# MineralFire.net
KiCad netlist of a schematic drawn in EAGLE
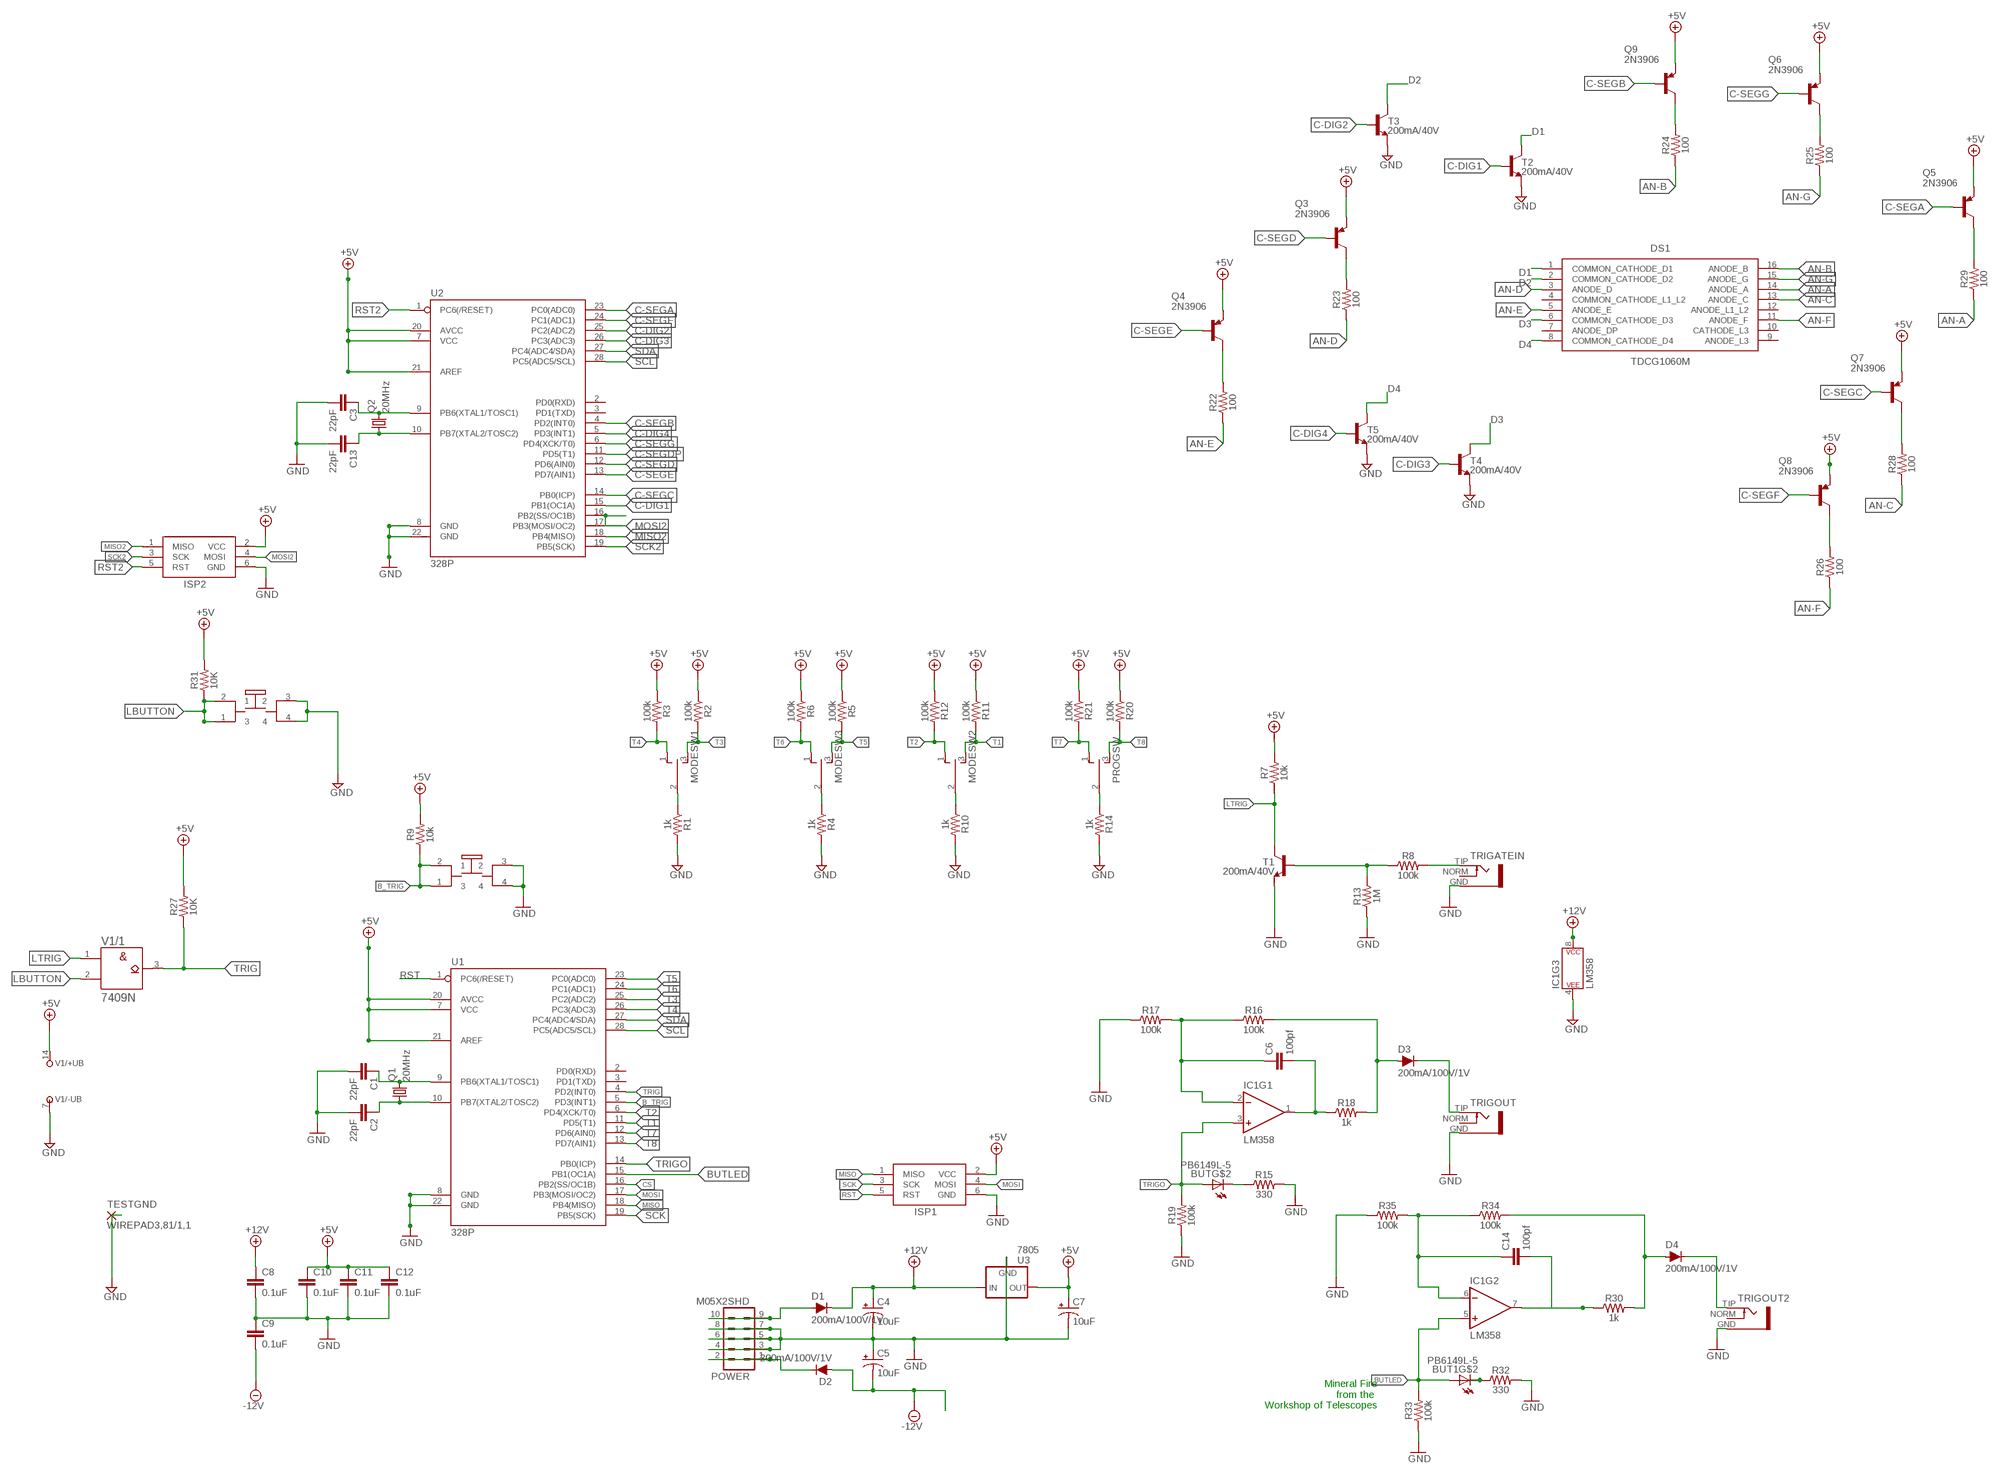
[diagram p0: schematic, sheet 1]

(export (version "E")
  (design (tool "Eeschema 10.0.6"))
  (components
    (comp (ref "BUT")
      (value "PB6149L-5")
      (footprint "eagle-import:PB6149L")
      (libsource (lib "eagle-import") (part "PB6149L-5"))
    )
    (comp (ref "BUT1")
      (value "PB6149L-5")
      (footprint "eagle-import:PB6149L")
      (libsource (lib "eagle-import") (part "PB6149L-5"))
    )
    (comp (ref "C1")
      (value "22pF")
      (footprint "eagle-import:CAP-PTH-2.54")
      (libsource (lib "eagle-import") (part "22PF-PTH-2.54MM-200V-5%"))
    )
    (comp (ref "C2")
      (value "22pF")
      (footprint "eagle-import:CAP-PTH-2.54")
      (libsource (lib "eagle-import") (part "22PF-PTH-2.54MM-200V-5%"))
    )
    (comp (ref "C3")
      (value "22pF")
      (footprint "eagle-import:CAP-PTH-2.54")
      (libsource (lib "eagle-import") (part "22PF-PTH-2.54MM-200V-5%"))
    )
    (comp (ref "C4")
      (value "10uF")
      (footprint "eagle-import:CPOL-RADIAL-2.5MM-5MM")
      (libsource (lib "eagle-import") (part "10UF-POLAR-RADIAL-2.5MM-25V-20%"))
    )
    (comp (ref "C5")
      (value "10uF")
      (footprint "eagle-import:CPOL-RADIAL-2.5MM-5MM")
      (libsource (lib "eagle-import") (part "10UF-POLAR-RADIAL-2.5MM-25V-20%"))
    )
    (comp (ref "C6")
      (value "100pf")
      (footprint "eagle-import:C075-032X103")
      (libsource (lib "eagle-import") (part "C-EU075-032X103"))
    )
    (comp (ref "C7")
      (value "10uF")
      (footprint "eagle-import:CPOL-RADIAL-2.5MM-5MM")
      (libsource (lib "eagle-import") (part "10UF-POLAR-RADIAL-2.5MM-25V-20%"))
    )
    (comp (ref "C8")
      (value "0.1uF")
      (footprint "eagle-import:CAP-PTH-SMALL-KIT")
      (libsource (lib "eagle-import") (part "0.1UF-KIT-EZ-50V-20%"))
    )
    (comp (ref "C9")
      (value "0.1uF")
      (footprint "eagle-import:CAP-PTH-SMALL-KIT")
      (libsource (lib "eagle-import") (part "0.1UF-KIT-EZ-50V-20%"))
    )
    (comp (ref "C10")
      (value "0.1uF")
      (footprint "eagle-import:CAP-PTH-SMALL-KIT")
      (libsource (lib "eagle-import") (part "0.1UF-KIT-EZ-50V-20%"))
    )
    (comp (ref "C11")
      (value "0.1uF")
      (footprint "eagle-import:CAP-PTH-SMALL-KIT")
      (libsource (lib "eagle-import") (part "0.1UF-KIT-EZ-50V-20%"))
    )
    (comp (ref "C12")
      (value "0.1uF")
      (footprint "eagle-import:CAP-PTH-SMALL-KIT")
      (libsource (lib "eagle-import") (part "0.1UF-KIT-EZ-50V-20%"))
    )
    (comp (ref "C13")
      (value "22pF")
      (footprint "eagle-import:CAP-PTH-2.54")
      (libsource (lib "eagle-import") (part "22PF-PTH-2.54MM-200V-5%"))
    )
    (comp (ref "C14")
      (value "100pf")
      (footprint "eagle-import:C075-032X103")
      (libsource (lib "eagle-import") (part "C-EU075-032X103"))
    )
    (comp (ref "D1")
      (value "200mA/100V/1V")
      (footprint "eagle-import:DIODE-1N4148")
      (libsource (lib "eagle-import") (part "DIODE-1N4148"))
    )
    (comp (ref "D2")
      (value "200mA/100V/1V")
      (footprint "eagle-import:DIODE-1N4148")
      (libsource (lib "eagle-import") (part "DIODE-1N4148"))
    )
    (comp (ref "D3")
      (value "200mA/100V/1V")
      (footprint "eagle-import:DIODE-1N4148")
      (libsource (lib "eagle-import") (part "DIODE-1N4148"))
    )
    (comp (ref "D4")
      (value "200mA/100V/1V")
      (footprint "eagle-import:DIODE-1N4148")
      (libsource (lib "eagle-import") (part "DIODE-1N4148"))
    )
    (comp (ref "DS1")
      (value "TDCG1060M")
      (footprint "eagle-import:DIPS1016W50P254L4020H700Q16N")
      (fields (field (name "RS_PART_NUMBER") "8187530P"))
      (libsource (lib "eagle-import") (part "TDCG1060M"))
    )
    (comp (ref "IC1")
      (value "LM358")
      (footprint "eagle-import:DIP08")
      (libsource (lib "eagle-import") (part "LM358"))
    )
    (comp (ref "ISP1")
      (value "AVRISP-6")
      (footprint "eagle-import:AVRISP")
      (libsource (lib "eagle-import") (part "AVRISP-6"))
    )
    (comp (ref "ISP2")
      (value "AVRISP-6")
      (footprint "eagle-import:AVRISP")
      (libsource (lib "eagle-import") (part "AVRISP-6"))
    )
    (comp (ref "MODESW1")
      (value "TOGGLE_ON_OFF_ON")
      (footprint "eagle-import:TOGGLE_ON_OFF_ON")
      (libsource (lib "eagle-import") (part "TOGGLE_ON_OFF_ON"))
    )
    (comp (ref "MODESW2")
      (value "TOGGLE_ON_OFF_ON")
      (footprint "eagle-import:TOGGLE_ON_OFF_ON")
      (libsource (lib "eagle-import") (part "TOGGLE_ON_OFF_ON"))
    )
    (comp (ref "MODESW3")
      (value "TOGGLE_ON_OFF_ON")
      (footprint "eagle-import:TOGGLE_ON_OFF_ON")
      (libsource (lib "eagle-import") (part "TOGGLE_ON_OFF_ON"))
    )
    (comp (ref "POWER")
      (value "M05X2SHD")
      (footprint "eagle-import:2X5-SHROUDED")
      (libsource (lib "eagle-import") (part "M05X2SHD"))
    )
    (comp (ref "PROGSW")
      (value "TOGGLE_ON_OFF_ON")
      (footprint "eagle-import:TOGGLE_ON_OFF_ON")
      (libsource (lib "eagle-import") (part "TOGGLE_ON_OFF_ON"))
    )
    (comp (ref "Q1")
      (value "20MHz")
      (footprint "eagle-import:HC49U70")
      (libsource (lib "eagle-import") (part "CRYSTALHC49U70"))
    )
    (comp (ref "Q2")
      (value "20MHz")
      (footprint "eagle-import:HC49U70")
      (libsource (lib "eagle-import") (part "CRYSTALHC49U70"))
    )
    (comp (ref "Q3")
      (value "2N3906")
      (footprint "eagle-import:TO92")
      (libsource (lib "eagle-import") (part "2N3906"))
    )
    (comp (ref "Q4")
      (value "2N3906")
      (footprint "eagle-import:TO92")
      (libsource (lib "eagle-import") (part "2N3906"))
    )
    (comp (ref "Q5")
      (value "2N3906")
      (footprint "eagle-import:TO92")
      (libsource (lib "eagle-import") (part "2N3906"))
    )
    (comp (ref "Q6")
      (value "2N3906")
      (footprint "eagle-import:TO92")
      (libsource (lib "eagle-import") (part "2N3906"))
    )
    (comp (ref "Q7")
      (value "2N3906")
      (footprint "eagle-import:TO92")
      (libsource (lib "eagle-import") (part "2N3906"))
    )
    (comp (ref "Q8")
      (value "2N3906")
      (footprint "eagle-import:TO92")
      (libsource (lib "eagle-import") (part "2N3906"))
    )
    (comp (ref "Q9")
      (value "2N3906")
      (footprint "eagle-import:TO92")
      (libsource (lib "eagle-import") (part "2N3906"))
    )
    (comp (ref "R1")
      (value "1k")
      (footprint "eagle-import:AXIAL-0.3")
      (libsource (lib "eagle-import") (part "1KOHM-HORIZ-1/4W-5%"))
    )
    (comp (ref "R2")
      (value "100k")
      (footprint "eagle-import:AXIAL-0.3")
      (libsource (lib "eagle-import") (part "100KOHM-HORIZ-1/4W-5%"))
    )
    (comp (ref "R3")
      (value "100k")
      (footprint "eagle-import:AXIAL-0.3")
      (libsource (lib "eagle-import") (part "100KOHM-HORIZ-1/4W-5%"))
    )
    (comp (ref "R4")
      (value "1k")
      (footprint "eagle-import:AXIAL-0.3")
      (libsource (lib "eagle-import") (part "1KOHM-HORIZ-1/4W-5%"))
    )
    (comp (ref "R5")
      (value "100k")
      (footprint "eagle-import:AXIAL-0.3")
      (libsource (lib "eagle-import") (part "100KOHM-HORIZ-1/4W-5%"))
    )
    (comp (ref "R6")
      (value "100k")
      (footprint "eagle-import:AXIAL-0.3")
      (libsource (lib "eagle-import") (part "100KOHM-HORIZ-1/4W-5%"))
    )
    (comp (ref "R7")
      (value "10k")
      (footprint "eagle-import:AXIAL-0.3")
      (libsource (lib "eagle-import") (part "10KOHM-HORIZ-1/4W-5%"))
    )
    (comp (ref "R8")
      (value "100k")
      (footprint "eagle-import:AXIAL-0.3")
      (libsource (lib "eagle-import") (part "100KOHM-HORIZ-1/4W-5%"))
    )
    (comp (ref "R9")
      (value "10k")
      (footprint "eagle-import:AXIAL-0.3")
      (libsource (lib "eagle-import") (part "10KOHM-HORIZ-1/4W-1%"))
    )
    (comp (ref "R10")
      (value "1k")
      (footprint "eagle-import:AXIAL-0.3")
      (libsource (lib "eagle-import") (part "1KOHM-HORIZ-1/4W-5%"))
    )
    (comp (ref "R11")
      (value "100k")
      (footprint "eagle-import:AXIAL-0.3")
      (libsource (lib "eagle-import") (part "100KOHM-HORIZ-1/4W-5%"))
    )
    (comp (ref "R12")
      (value "100k")
      (footprint "eagle-import:AXIAL-0.3")
      (libsource (lib "eagle-import") (part "100KOHM-HORIZ-1/4W-5%"))
    )
    (comp (ref "R13")
      (value "1M")
      (footprint "eagle-import:AXIAL-0.3")
      (libsource (lib "eagle-import") (part "1MOHM-HORIZ-1/4W-5%"))
    )
    (comp (ref "R14")
      (value "1k")
      (footprint "eagle-import:AXIAL-0.3")
      (libsource (lib "eagle-import") (part "1KOHM-HORIZ-1/4W-5%"))
    )
    (comp (ref "R15")
      (value "330")
      (footprint "eagle-import:AXIAL-0.3")
      (libsource (lib "eagle-import") (part "330OHM-HORIZ-1/10W-5%"))
    )
    (comp (ref "R16")
      (value "100k")
      (footprint "eagle-import:AXIAL-0.3")
      (libsource (lib "eagle-import") (part "100KOHM-HORIZ-1/4W-5%"))
    )
    (comp (ref "R17")
      (value "100k")
      (footprint "eagle-import:AXIAL-0.3")
      (libsource (lib "eagle-import") (part "100KOHM-HORIZ-1/4W-5%"))
    )
    (comp (ref "R18")
      (value "1k")
      (footprint "eagle-import:AXIAL-0.3")
      (libsource (lib "eagle-import") (part "1KOHM-HORIZ-1/4W-5%"))
    )
    (comp (ref "R19")
      (value "100k")
      (footprint "eagle-import:AXIAL-0.3")
      (libsource (lib "eagle-import") (part "100KOHM-HORIZ-1/4W-5%"))
    )
    (comp (ref "R20")
      (value "100k")
      (footprint "eagle-import:AXIAL-0.3")
      (libsource (lib "eagle-import") (part "100KOHM-HORIZ-1/4W-5%"))
    )
    (comp (ref "R21")
      (value "100k")
      (footprint "eagle-import:AXIAL-0.3")
      (libsource (lib "eagle-import") (part "100KOHM-HORIZ-1/4W-5%"))
    )
    (comp (ref "R22")
      (value "100")
      (footprint "eagle-import:AXIAL-0.3EZ")
      (libsource (lib "eagle-import") (part "100OHM-HORIZ_KIT-1/4W-1%"))
    )
    (comp (ref "R23")
      (value "100")
      (footprint "eagle-import:AXIAL-0.3EZ")
      (libsource (lib "eagle-import") (part "100OHM-HORIZ_KIT-1/4W-1%"))
    )
    (comp (ref "R24")
      (value "100")
      (footprint "eagle-import:AXIAL-0.3EZ")
      (libsource (lib "eagle-import") (part "100OHM-HORIZ_KIT-1/4W-1%"))
    )
    (comp (ref "R25")
      (value "100")
      (footprint "eagle-import:AXIAL-0.3EZ")
      (libsource (lib "eagle-import") (part "100OHM-HORIZ_KIT-1/4W-1%"))
    )
    (comp (ref "R26")
      (value "100")
      (footprint "eagle-import:AXIAL-0.3EZ")
      (libsource (lib "eagle-import") (part "100OHM-HORIZ_KIT-1/4W-1%"))
    )
    (comp (ref "R27")
      (value "10K")
      (footprint "eagle-import:AXIAL-0.3EZ")
      (libsource (lib "eagle-import") (part "100OHM-HORIZ_KIT-1/4W-1%"))
    )
    (comp (ref "R28")
      (value "100")
      (footprint "eagle-import:AXIAL-0.3EZ")
      (libsource (lib "eagle-import") (part "100OHM-HORIZ_KIT-1/4W-1%"))
    )
    (comp (ref "R29")
      (value "100")
      (footprint "eagle-import:AXIAL-0.3EZ")
      (libsource (lib "eagle-import") (part "100OHM-HORIZ_KIT-1/4W-1%"))
    )
    (comp (ref "R30")
      (value "1k")
      (footprint "eagle-import:AXIAL-0.3")
      (libsource (lib "eagle-import") (part "1KOHM-HORIZ-1/4W-5%"))
    )
    (comp (ref "R31")
      (value "10K")
      (footprint "eagle-import:AXIAL-0.3EZ")
      (libsource (lib "eagle-import") (part "100OHM-HORIZ_KIT-1/4W-1%"))
    )
    (comp (ref "R32")
      (value "330")
      (footprint "eagle-import:AXIAL-0.3")
      (libsource (lib "eagle-import") (part "330OHM-HORIZ-1/10W-5%"))
    )
    (comp (ref "R33")
      (value "100k")
      (footprint "eagle-import:AXIAL-0.3")
      (libsource (lib "eagle-import") (part "100KOHM-HORIZ-1/4W-5%"))
    )
    (comp (ref "R34")
      (value "100k")
      (footprint "eagle-import:AXIAL-0.3")
      (libsource (lib "eagle-import") (part "100KOHM-HORIZ-1/4W-5%"))
    )
    (comp (ref "R35")
      (value "100k")
      (footprint "eagle-import:AXIAL-0.3")
      (libsource (lib "eagle-import") (part "100KOHM-HORIZ-1/4W-5%"))
    )
    (comp (ref "T1")
      (value "200mA/40V")
      (footprint "eagle-import:TO-92")
      (libsource (lib "eagle-import") (part "TRANS_NPN-2N3904"))
    )
    (comp (ref "T2")
      (value "200mA/40V")
      (footprint "eagle-import:TO-92")
      (libsource (lib "eagle-import") (part "TRANS_NPN-2N3904"))
    )
    (comp (ref "T3")
      (value "200mA/40V")
      (footprint "eagle-import:TO-92")
      (libsource (lib "eagle-import") (part "TRANS_NPN-2N3904"))
    )
    (comp (ref "T4")
      (value "200mA/40V")
      (footprint "eagle-import:TO-92")
      (libsource (lib "eagle-import") (part "TRANS_NPN-2N3904"))
    )
    (comp (ref "T5")
      (value "200mA/40V")
      (footprint "eagle-import:TO-92")
      (libsource (lib "eagle-import") (part "TRANS_NPN-2N3904"))
    )
    (comp (ref "TESTGND")
      (value "WIREPAD3,81/1,1")
      (footprint "eagle-import:3,81_1,1")
      (libsource (lib "eagle-import") (part "WIREPAD3,81/1,1"))
    )
    (comp (ref "TRIGATEIN")
      (value "S_JACK")
      (footprint "eagle-import:S_JACK")
      (libsource (lib "eagle-import") (part "S_JACK"))
    )
    (comp (ref "TRIGOUT")
      (value "S_JACK")
      (footprint "eagle-import:S_JACK")
      (libsource (lib "eagle-import") (part "S_JACK"))
    )
    (comp (ref "TRIGOUT2")
      (value "S_JACK")
      (footprint "eagle-import:S_JACK")
      (libsource (lib "eagle-import") (part "S_JACK"))
    )
    (comp (ref "U1")
      (value "328P")
      (footprint "eagle-import:DIP28")
      (libsource (lib "eagle-import") (part "ATMEGA328P_PDIP"))
    )
    (comp (ref "U2")
      (value "328P")
      (footprint "eagle-import:DIP28")
      (libsource (lib "eagle-import") (part "ATMEGA328P_PDIP"))
    )
    (comp (ref "U3")
      (value "7805")
      (footprint "eagle-import:TO-220-ALT")
      (libsource (lib "eagle-import") (part "V_REG_78XX-TO-220"))
    )
    (comp (ref "V1")
      (value "7409N")
      (footprint "eagle-import:DIL14")
      (libsource (lib "eagle-import") (part "7409N"))
    )
  )
  (nets
    (net (code "1") (name "+5V") (class "Default")
      (node (ref "C10") (pin "1") (pinfunction "1_1") (pintype "passive"))
      (node (ref "C11") (pin "1") (pinfunction "1_1") (pintype "passive"))
      (node (ref "C12") (pin "1") (pinfunction "1_1") (pintype "passive"))
      (node (ref "C7") (pin "1") (pinfunction "+_1") (pintype "passive"))
      (node (ref "ISP1") (pin "2") (pinfunction "VCC_2") (pintype "power_in"))
      (node (ref "ISP2") (pin "2") (pinfunction "VCC_2") (pintype "power_in"))
      (node (ref "Q3") (pin "3") (pinfunction "E_3") (pintype "passive"))
      (node (ref "Q4") (pin "3") (pinfunction "E_3") (pintype "passive"))
      (node (ref "Q5") (pin "3") (pinfunction "E_3") (pintype "passive"))
      (node (ref "Q6") (pin "3") (pinfunction "E_3") (pintype "passive"))
      (node (ref "Q7") (pin "3") (pinfunction "E_3") (pintype "passive"))
      (node (ref "Q8") (pin "3") (pinfunction "E_3") (pintype "passive"))
      (node (ref "Q9") (pin "3") (pinfunction "E_3") (pintype "passive"))
      (node (ref "R11") (pin "P$1") (pinfunction "1_P$1") (pintype "passive"))
      (node (ref "R12") (pin "P$1") (pinfunction "1_P$1") (pintype "passive"))
      (node (ref "R2") (pin "P$1") (pinfunction "1_P$1") (pintype "passive"))
      (node (ref "R20") (pin "P$1") (pinfunction "1_P$1") (pintype "passive"))
      (node (ref "R21") (pin "P$1") (pinfunction "1_P$1") (pintype "passive"))
      (node (ref "R27") (pin "P$2") (pinfunction "2_P$2") (pintype "passive"))
      (node (ref "R3") (pin "P$1") (pinfunction "1_P$1") (pintype "passive"))
      (node (ref "R31") (pin "P$2") (pinfunction "2_P$2") (pintype "passive"))
      (node (ref "R5") (pin "P$1") (pinfunction "1_P$1") (pintype "passive"))
      (node (ref "R6") (pin "P$1") (pinfunction "1_P$1") (pintype "passive"))
      (node (ref "R7") (pin "P$2") (pinfunction "2_P$2") (pintype "passive"))
      (node (ref "R9") (pin "P$2") (pinfunction "2_P$2") (pintype "passive"))
      (node (ref "U1") (pin "20") (pinfunction "AVCC_20") (pintype "bidirectional"))
      (node (ref "U1") (pin "21") (pinfunction "AREF_21") (pintype "bidirectional"))
      (node (ref "U1") (pin "7") (pinfunction "VCC_7") (pintype "bidirectional"))
      (node (ref "U2") (pin "20") (pinfunction "AVCC_20") (pintype "bidirectional"))
      (node (ref "U2") (pin "21") (pinfunction "AREF_21") (pintype "bidirectional"))
      (node (ref "U2") (pin "7") (pinfunction "VCC_7") (pintype "bidirectional"))
      (node (ref "U3") (pin "OUT") (pinfunction "OUT_OUT") (pintype "passive"))
      (node (ref "V1") (pin "14") (pinfunction "+UB_14") (pintype "power_in"))
    )
    (net (code "2") (name "+12V") (class "Default")
      (node (ref "C4") (pin "1") (pinfunction "+_1") (pintype "passive"))
      (node (ref "C8") (pin "1") (pinfunction "1_1") (pintype "passive"))
      (node (ref "D1") (pin "C") (pinfunction "C_C") (pintype "passive"))
      (node (ref "IC1") (pin "8") (pinfunction "P$V+_8") (pintype "bidirectional"))
      (node (ref "U3") (pin "IN") (pinfunction "IN_IN") (pintype "input"))
    )
    (net (code "3") (name "-12V") (class "Default")
      (node (ref "C5") (pin "2") (pinfunction "-_2") (pintype "passive"))
      (node (ref "C9") (pin "2") (pinfunction "2_2") (pintype "passive"))
      (node (ref "D2") (pin "A") (pinfunction "A_A") (pintype "passive"))
    )
    (net (code "4") (name "/D1") (class "Default")
      (node (ref "DS1") (pin "1") (pinfunction "COMMON_CATHODE_D1_1") (pintype "input"))
      (node (ref "T2") (pin "3") (pinfunction "C_3") (pintype "passive"))
    )
    (net (code "5") (name "/D2") (class "Default")
      (node (ref "DS1") (pin "2") (pinfunction "COMMON_CATHODE_D2_2") (pintype "input"))
      (node (ref "T3") (pin "3") (pinfunction "C_3") (pintype "passive"))
    )
    (net (code "6") (name "/D3") (class "Default")
      (node (ref "DS1") (pin "6") (pinfunction "COMMON_CATHODE_D3_6") (pintype "input"))
      (node (ref "T4") (pin "3") (pinfunction "C_3") (pintype "passive"))
    )
    (net (code "7") (name "/D4") (class "Default")
      (node (ref "DS1") (pin "8") (pinfunction "COMMON_CATHODE_D4_8") (pintype "input"))
      (node (ref "T5") (pin "3") (pinfunction "C_3") (pintype "passive"))
    )
    (net (code "8") (name "AN-A") (class "Default")
      (node (ref "DS1") (pin "14") (pinfunction "ANODE_A_14") (pintype "input"))
      (node (ref "R29") (pin "P$1") (pinfunction "1_P$1") (pintype "passive"))
    )
    (net (code "9") (name "AN-B") (class "Default")
      (node (ref "DS1") (pin "16") (pinfunction "ANODE_B_16") (pintype "input"))
      (node (ref "R24") (pin "P$1") (pinfunction "1_P$1") (pintype "passive"))
    )
    (net (code "10") (name "AN-C") (class "Default")
      (node (ref "DS1") (pin "13") (pinfunction "ANODE_C_13") (pintype "input"))
      (node (ref "R28") (pin "P$1") (pinfunction "1_P$1") (pintype "passive"))
    )
    (net (code "11") (name "AN-D") (class "Default")
      (node (ref "DS1") (pin "3") (pinfunction "ANODE_D_3") (pintype "input"))
      (node (ref "R23") (pin "P$1") (pinfunction "1_P$1") (pintype "passive"))
    )
    (net (code "12") (name "AN-E") (class "Default")
      (node (ref "DS1") (pin "5") (pinfunction "ANODE_E_5") (pintype "input"))
      (node (ref "R22") (pin "P$1") (pinfunction "1_P$1") (pintype "passive"))
    )
    (net (code "13") (name "AN-F") (class "Default")
      (node (ref "DS1") (pin "11") (pinfunction "ANODE_F_11") (pintype "input"))
      (node (ref "R26") (pin "P$1") (pinfunction "1_P$1") (pintype "passive"))
    )
    (net (code "14") (name "AN-G") (class "Default")
      (node (ref "DS1") (pin "15") (pinfunction "ANODE_G_15") (pintype "input"))
      (node (ref "R25") (pin "P$1") (pinfunction "1_P$1") (pintype "passive"))
    )
    (net (code "15") (name "BUTLED") (class "Default")
      (node (ref "BUT1") (pin "A") (pinfunction "A_A") (pintype "passive"))
      (node (ref "IC1") (pin "5") (pinfunction "+IN_5") (pintype "input"))
      (node (ref "R33") (pin "P$2") (pinfunction "2_P$2") (pintype "passive"))
      (node (ref "U1") (pin "15") (pinfunction "PB1(OC1A)_15") (pintype "bidirectional"))
    )
    (net (code "16") (name "B_TRIG") (class "Default")
      (node (ref "BUT") (pin "1") (pinfunction "3_1") (pintype "bidirectional"))
      (node (ref "BUT") (pin "2") (pinfunction "1_2") (pintype "bidirectional"))
      (node (ref "R9") (pin "P$1") (pinfunction "1_P$1") (pintype "passive"))
      (node (ref "U1") (pin "5") (pinfunction "PD3(INT1)_5") (pintype "bidirectional"))
    )
    (net (code "17") (name "C-DIG1") (class "Default")
      (node (ref "T2") (pin "2") (pinfunction "B_2") (pintype "passive"))
      (node (ref "U2") (pin "15") (pinfunction "PB1(OC1A)_15") (pintype "bidirectional"))
    )
    (net (code "18") (name "C-DIG2") (class "Default")
      (node (ref "T3") (pin "2") (pinfunction "B_2") (pintype "passive"))
      (node (ref "U2") (pin "25") (pinfunction "PC2(ADC2)_25") (pintype "bidirectional"))
    )
    (net (code "19") (name "C-DIG3") (class "Default")
      (node (ref "T4") (pin "2") (pinfunction "B_2") (pintype "passive"))
      (node (ref "U2") (pin "26") (pinfunction "PC3(ADC3)_26") (pintype "bidirectional"))
    )
    (net (code "20") (name "C-DIG4") (class "Default")
      (node (ref "T5") (pin "2") (pinfunction "B_2") (pintype "passive"))
      (node (ref "U2") (pin "5") (pinfunction "PD3(INT1)_5") (pintype "bidirectional"))
    )
    (net (code "21") (name "C-SEGA") (class "Default")
      (node (ref "Q5") (pin "2") (pinfunction "B_2") (pintype "passive"))
      (node (ref "U2") (pin "23") (pinfunction "PC0(ADC0)_23") (pintype "bidirectional"))
    )
    (net (code "22") (name "C-SEGB") (class "Default")
      (node (ref "Q9") (pin "2") (pinfunction "B_2") (pintype "passive"))
      (node (ref "U2") (pin "4") (pinfunction "PD2(INT0)_4") (pintype "bidirectional"))
    )
    (net (code "23") (name "C-SEGC") (class "Default")
      (node (ref "Q7") (pin "2") (pinfunction "B_2") (pintype "passive"))
      (node (ref "U2") (pin "14") (pinfunction "PB0(ICP)_14") (pintype "bidirectional"))
    )
    (net (code "24") (name "C-SEGD") (class "Default")
      (node (ref "Q3") (pin "2") (pinfunction "B_2") (pintype "passive"))
      (node (ref "U2") (pin "12") (pinfunction "PD6(AIN0)_12") (pintype "bidirectional"))
    )
    (net (code "25") (name "C-SEGDP") (class "Default")
      (node (ref "U2") (pin "11") (pinfunction "PD5(T1)_11") (pintype "bidirectional"))
    )
    (net (code "26") (name "C-SEGE") (class "Default")
      (node (ref "Q4") (pin "2") (pinfunction "B_2") (pintype "passive"))
      (node (ref "U2") (pin "13") (pinfunction "PD7(AIN1)_13") (pintype "bidirectional"))
    )
    (net (code "27") (name "C-SEGF") (class "Default")
      (node (ref "Q8") (pin "2") (pinfunction "B_2") (pintype "passive"))
      (node (ref "U2") (pin "24") (pinfunction "PC1(ADC1)_24") (pintype "bidirectional"))
    )
    (net (code "28") (name "C-SEGG") (class "Default")
      (node (ref "Q6") (pin "2") (pinfunction "B_2") (pintype "passive"))
      (node (ref "U2") (pin "6") (pinfunction "PD4(XCK/T0)_6") (pintype "bidirectional"))
    )
    (net (code "29") (name "CS") (class "Default")
      (node (ref "U1") (pin "16") (pinfunction "PB2(SS/OC1B)_16") (pintype "bidirectional"))
    )
    (net (code "30") (name "GND") (class "Default")
      (node (ref "BUT") (pin "3") (pinfunction "2_3") (pintype "bidirectional"))
      (node (ref "BUT") (pin "4") (pinfunction "4_4") (pintype "bidirectional"))
      (node (ref "BUT1") (pin "3") (pinfunction "2_3") (pintype "bidirectional"))
      (node (ref "BUT1") (pin "4") (pinfunction "4_4") (pintype "bidirectional"))
      (node (ref "C1") (pin "2") (pinfunction "2_2") (pintype "passive"))
      (node (ref "C10") (pin "2") (pinfunction "2_2") (pintype "passive"))
      (node (ref "C11") (pin "2") (pinfunction "2_2") (pintype "passive"))
      (node (ref "C12") (pin "2") (pinfunction "2_2") (pintype "passive"))
      (node (ref "C13") (pin "2") (pinfunction "2_2") (pintype "passive"))
      (node (ref "C2") (pin "2") (pinfunction "2_2") (pintype "passive"))
      (node (ref "C3") (pin "2") (pinfunction "2_2") (pintype "passive"))
      (node (ref "C4") (pin "2") (pinfunction "-_2") (pintype "passive"))
      (node (ref "C5") (pin "1") (pinfunction "+_1") (pintype "passive"))
      (node (ref "C7") (pin "2") (pinfunction "-_2") (pintype "passive"))
      (node (ref "C8") (pin "2") (pinfunction "2_2") (pintype "passive"))
      (node (ref "C9") (pin "1") (pinfunction "1_1") (pintype "passive"))
      (node (ref "IC1") (pin "4") (pinfunction "P$V-_4") (pintype "bidirectional"))
      (node (ref "ISP1") (pin "6") (pinfunction "GND_6") (pintype "power_in"))
      (node (ref "ISP2") (pin "6") (pinfunction "GND_6") (pintype "power_in"))
      (node (ref "POWER") (pin "3") (pinfunction "3_3") (pintype "passive"))
      (node (ref "POWER") (pin "4") (pinfunction "4_4") (pintype "passive"))
      (node (ref "POWER") (pin "5") (pinfunction "5_5") (pintype "passive"))
      (node (ref "POWER") (pin "6") (pinfunction "6_6") (pintype "passive"))
      (node (ref "POWER") (pin "7") (pinfunction "7_7") (pintype "passive"))
      (node (ref "POWER") (pin "8") (pinfunction "8_8") (pintype "passive"))
      (node (ref "R1") (pin "P$2") (pinfunction "2_P$2") (pintype "passive"))
      (node (ref "R10") (pin "P$2") (pinfunction "2_P$2") (pintype "passive"))
      (node (ref "R13") (pin "P$1") (pinfunction "1_P$1") (pintype "passive"))
      (node (ref "R14") (pin "P$2") (pinfunction "2_P$2") (pintype "passive"))
      (node (ref "R15") (pin "P$2") (pinfunction "2_P$2") (pintype "passive"))
      (node (ref "R17") (pin "P$1") (pinfunction "1_P$1") (pintype "passive"))
      (node (ref "R19") (pin "P$1") (pinfunction "1_P$1") (pintype "passive"))
      (node (ref "R32") (pin "P$2") (pinfunction "2_P$2") (pintype "passive"))
      (node (ref "R33") (pin "P$1") (pinfunction "1_P$1") (pintype "passive"))
      (node (ref "R35") (pin "P$1") (pinfunction "1_P$1") (pintype "passive"))
      (node (ref "R4") (pin "P$2") (pinfunction "2_P$2") (pintype "passive"))
      (node (ref "T1") (pin "1") (pinfunction "E_1") (pintype "passive"))
      (node (ref "T2") (pin "1") (pinfunction "E_1") (pintype "passive"))
      (node (ref "T3") (pin "1") (pinfunction "E_1") (pintype "passive"))
      (node (ref "T4") (pin "1") (pinfunction "E_1") (pintype "passive"))
      (node (ref "T5") (pin "1") (pinfunction "E_1") (pintype "passive"))
      (node (ref "TESTGND") (pin "1") (pinfunction "P_1") (pintype "passive"))
      (node (ref "TRIGATEIN") (pin "GND") (pinfunction "GND_GND") (pintype "passive"))
      (node (ref "TRIGOUT") (pin "GND") (pinfunction "GND_GND") (pintype "passive"))
      (node (ref "TRIGOUT2") (pin "GND") (pinfunction "GND_GND") (pintype "passive"))
      (node (ref "U1") (pin "22") (pinfunction "GND_22") (pintype "bidirectional"))
      (node (ref "U1") (pin "8") (pinfunction "GND_8") (pintype "bidirectional"))
      (node (ref "U2") (pin "22") (pinfunction "GND_22") (pintype "bidirectional"))
      (node (ref "U2") (pin "8") (pinfunction "GND_8") (pintype "bidirectional"))
      (node (ref "U3") (pin "GND") (pinfunction "GND_GND") (pintype "input"))
      (node (ref "V1") (pin "7") (pinfunction "-UB_7") (pintype "power_in"))
    )
    (net (code "31") (name "LBUTTON") (class "Default")
      (node (ref "BUT1") (pin "1") (pinfunction "3_1") (pintype "bidirectional"))
      (node (ref "BUT1") (pin "2") (pinfunction "1_2") (pintype "bidirectional"))
      (node (ref "R31") (pin "P$1") (pinfunction "1_P$1") (pintype "passive"))
      (node (ref "V1") (pin "2") (pinfunction "B_2") (pintype "input"))
    )
    (net (code "32") (name "LTRIG") (class "Default")
      (node (ref "R7") (pin "P$1") (pinfunction "1_P$1") (pintype "passive"))
      (node (ref "T1") (pin "3") (pinfunction "C_3") (pintype "passive"))
      (node (ref "V1") (pin "1") (pinfunction "A_1") (pintype "input"))
    )
    (net (code "33") (name "MISO") (class "Default")
      (node (ref "ISP1") (pin "1") (pinfunction "MISO_1") (pintype "input"))
      (node (ref "U1") (pin "18") (pinfunction "PB4(MISO)_18") (pintype "bidirectional"))
    )
    (net (code "34") (name "MISO2") (class "Default")
      (node (ref "ISP2") (pin "1") (pinfunction "MISO_1") (pintype "input"))
      (node (ref "U2") (pin "18") (pinfunction "PB4(MISO)_18") (pintype "bidirectional"))
    )
    (net (code "35") (name "MOSI") (class "Default")
      (node (ref "ISP1") (pin "4") (pinfunction "MOSI_4") (pintype "output"))
      (node (ref "U1") (pin "17") (pinfunction "PB3(MOSI/OC2)_17") (pintype "bidirectional"))
    )
    (net (code "36") (name "MOSI2") (class "Default")
      (node (ref "ISP2") (pin "4") (pinfunction "MOSI_4") (pintype "output"))
      (node (ref "U2") (pin "16") (pinfunction "PB2(SS/OC1B)_16") (pintype "bidirectional"))
      (node (ref "U2") (pin "17") (pinfunction "PB3(MOSI/OC2)_17") (pintype "bidirectional"))
    )
    (net (code "37") (name "Net-(BUT1B-C)") (class "Default")
      (node (ref "BUT1") (pin "K") (pinfunction "C_K") (pintype "passive"))
      (node (ref "R32") (pin "P$1") (pinfunction "1_P$1") (pintype "passive"))
    )
    (net (code "38") (name "Net-(BUTB-C)") (class "Default")
      (node (ref "BUT") (pin "K") (pinfunction "C_K") (pintype "passive"))
      (node (ref "R15") (pin "P$1") (pinfunction "1_P$1") (pintype "passive"))
    )
    (net (code "39") (name "Net-(D1-PadA)") (class "Default")
      (node (ref "D1") (pin "A") (pinfunction "A_A") (pintype "passive"))
      (node (ref "POWER") (pin "10") (pinfunction "10_10") (pintype "passive"))
      (node (ref "POWER") (pin "9") (pinfunction "9_9") (pintype "passive"))
    )
    (net (code "40") (name "Net-(D2-PadC)") (class "Default")
      (node (ref "D2") (pin "C") (pinfunction "C_C") (pintype "passive"))
      (node (ref "POWER") (pin "1") (pinfunction "1_1") (pintype "passive"))
      (node (ref "POWER") (pin "2") (pinfunction "2_2") (pintype "passive"))
    )
    (net (code "41") (name "Net-(D3-PadC)") (class "Default")
      (node (ref "D3") (pin "C") (pinfunction "C_C") (pintype "passive"))
      (node (ref "TRIGOUT") (pin "TIP") (pinfunction "TIP_TIP") (pintype "passive"))
    )
    (net (code "42") (name "Net-(D4-PadC)") (class "Default")
      (node (ref "D4") (pin "C") (pinfunction "C_C") (pintype "passive"))
      (node (ref "TRIGOUT2") (pin "TIP") (pinfunction "TIP_TIP") (pintype "passive"))
    )
    (net (code "43") (name "Net-(IC1A--IN)") (class "Default")
      (node (ref "C6") (pin "1") (pinfunction "1_1") (pintype "passive"))
      (node (ref "IC1") (pin "2") (pinfunction "-IN_2") (pintype "input"))
      (node (ref "R16") (pin "P$1") (pinfunction "1_P$1") (pintype "passive"))
      (node (ref "R17") (pin "P$2") (pinfunction "2_P$2") (pintype "passive"))
    )
    (net (code "44") (name "Net-(IC1A-OUT)") (class "Default")
      (node (ref "C6") (pin "2") (pinfunction "2_2") (pintype "passive"))
      (node (ref "IC1") (pin "1") (pinfunction "OUT_1") (pintype "output"))
      (node (ref "R18") (pin "P$1") (pinfunction "1_P$1") (pintype "passive"))
    )
    (net (code "45") (name "Net-(IC1B--IN)") (class "Default")
      (node (ref "C14") (pin "1") (pinfunction "1_1") (pintype "passive"))
      (node (ref "IC1") (pin "6") (pinfunction "-IN_6") (pintype "input"))
      (node (ref "R34") (pin "P$1") (pinfunction "1_P$1") (pintype "passive"))
      (node (ref "R35") (pin "P$2") (pinfunction "2_P$2") (pintype "passive"))
    )
    (net (code "46") (name "Net-(IC1B-OUT)") (class "Default")
      (node (ref "IC1") (pin "7") (pinfunction "OUT_7") (pintype "output"))
      (node (ref "R30") (pin "P$1") (pinfunction "1_P$1") (pintype "passive"))
    )
    (net (code "47") (name "Net-(MODESW1-P)") (class "Default")
      (node (ref "MODESW1") (pin "2") (pinfunction "P_2") (pintype "passive"))
      (node (ref "R1") (pin "P$1") (pinfunction "1_P$1") (pintype "passive"))
    )
    (net (code "48") (name "Net-(MODESW2-P)") (class "Default")
      (node (ref "MODESW2") (pin "2") (pinfunction "P_2") (pintype "passive"))
      (node (ref "R10") (pin "P$1") (pinfunction "1_P$1") (pintype "passive"))
    )
    (net (code "49") (name "Net-(MODESW3-P)") (class "Default")
      (node (ref "MODESW3") (pin "2") (pinfunction "P_2") (pintype "passive"))
      (node (ref "R4") (pin "P$1") (pinfunction "1_P$1") (pintype "passive"))
    )
    (net (code "50") (name "Net-(PROGSW-P)") (class "Default")
      (node (ref "PROGSW") (pin "2") (pinfunction "P_2") (pintype "passive"))
      (node (ref "R14") (pin "P$1") (pinfunction "1_P$1") (pintype "passive"))
    )
    (net (code "51") (name "Net-(Q3-C)") (class "Default")
      (node (ref "Q3") (pin "1") (pinfunction "C_1") (pintype "passive"))
      (node (ref "R23") (pin "P$2") (pinfunction "2_P$2") (pintype "passive"))
    )
    (net (code "52") (name "Net-(Q4-C)") (class "Default")
      (node (ref "Q4") (pin "1") (pinfunction "C_1") (pintype "passive"))
      (node (ref "R22") (pin "P$2") (pinfunction "2_P$2") (pintype "passive"))
    )
    (net (code "53") (name "Net-(Q5-C)") (class "Default")
      (node (ref "Q5") (pin "1") (pinfunction "C_1") (pintype "passive"))
      (node (ref "R29") (pin "P$2") (pinfunction "2_P$2") (pintype "passive"))
    )
    (net (code "54") (name "Net-(Q6-C)") (class "Default")
      (node (ref "Q6") (pin "1") (pinfunction "C_1") (pintype "passive"))
      (node (ref "R25") (pin "P$2") (pinfunction "2_P$2") (pintype "passive"))
    )
    (net (code "55") (name "Net-(Q7-C)") (class "Default")
      (node (ref "Q7") (pin "1") (pinfunction "C_1") (pintype "passive"))
      (node (ref "R28") (pin "P$2") (pinfunction "2_P$2") (pintype "passive"))
    )
    (net (code "56") (name "Net-(Q8-C)") (class "Default")
      (node (ref "Q8") (pin "1") (pinfunction "C_1") (pintype "passive"))
      (node (ref "R26") (pin "P$2") (pinfunction "2_P$2") (pintype "passive"))
    )
    (net (code "57") (name "Net-(Q9-C)") (class "Default")
      (node (ref "Q9") (pin "1") (pinfunction "C_1") (pintype "passive"))
      (node (ref "R24") (pin "P$2") (pinfunction "2_P$2") (pintype "passive"))
    )
    (net (code "58") (name "Net-(R8-2)") (class "Default")
      (node (ref "R8") (pin "P$2") (pinfunction "2_P$2") (pintype "passive"))
      (node (ref "TRIGATEIN") (pin "TIP") (pinfunction "TIP_TIP") (pintype "passive"))
    )
    (net (code "59") (name "Net-(R13-2)") (class "Default")
      (node (ref "R13") (pin "P$2") (pinfunction "2_P$2") (pintype "passive"))
      (node (ref "R8") (pin "P$1") (pinfunction "1_P$1") (pintype "passive"))
      (node (ref "T1") (pin "2") (pinfunction "B_2") (pintype "passive"))
    )
    (net (code "60") (name "Net-(R16-2)") (class "Default")
      (node (ref "D3") (pin "A") (pinfunction "A_A") (pintype "passive"))
      (node (ref "R16") (pin "P$2") (pinfunction "2_P$2") (pintype "passive"))
      (node (ref "R18") (pin "P$2") (pinfunction "2_P$2") (pintype "passive"))
    )
    (net (code "61") (name "Net-(R30-2)") (class "Default")
      (node (ref "D4") (pin "A") (pinfunction "A_A") (pintype "passive"))
      (node (ref "R30") (pin "P$2") (pinfunction "2_P$2") (pintype "passive"))
    )
    (net (code "62") (name "Net-(U1-PB6(XTAL1{slash}TOSC1))") (class "Default")
      (node (ref "C1") (pin "1") (pinfunction "1_1") (pintype "passive"))
      (node (ref "Q1") (pin "2") (pinfunction "2_2") (pintype "passive"))
      (node (ref "U1") (pin "9") (pinfunction "PB6(XTAL1/TOSC1)_9") (pintype "bidirectional"))
    )
    (net (code "63") (name "Net-(U1-PB7(XTAL2{slash}TOSC2))") (class "Default")
      (node (ref "C2") (pin "1") (pinfunction "1_1") (pintype "passive"))
      (node (ref "Q1") (pin "1") (pinfunction "1_1") (pintype "passive"))
      (node (ref "U1") (pin "10") (pinfunction "PB7(XTAL2/TOSC2)_10") (pintype "bidirectional"))
    )
    (net (code "64") (name "Net-(U2-PB6(XTAL1{slash}TOSC1))") (class "Default")
      (node (ref "C3") (pin "1") (pinfunction "1_1") (pintype "passive"))
      (node (ref "Q2") (pin "2") (pinfunction "2_2") (pintype "passive"))
      (node (ref "U2") (pin "9") (pinfunction "PB6(XTAL1/TOSC1)_9") (pintype "bidirectional"))
    )
    (net (code "65") (name "Net-(U2-PB7(XTAL2{slash}TOSC2))") (class "Default")
      (node (ref "C13") (pin "1") (pinfunction "1_1") (pintype "passive"))
      (node (ref "Q2") (pin "1") (pinfunction "1_1") (pintype "passive"))
      (node (ref "U2") (pin "10") (pinfunction "PB7(XTAL2/TOSC2)_10") (pintype "bidirectional"))
    )
    (net (code "66") (name "RST") (class "Default")
      (node (ref "ISP1") (pin "5") (pinfunction "RST_5") (pintype "output"))
      (node (ref "U1") (pin "1") (pinfunction "PC6(/RESET)_1") (pintype "bidirectional"))
    )
    (net (code "67") (name "RST2") (class "Default")
      (node (ref "ISP2") (pin "5") (pinfunction "RST_5") (pintype "output"))
      (node (ref "U2") (pin "1") (pinfunction "PC6(/RESET)_1") (pintype "bidirectional"))
    )
    (net (code "68") (name "SCK") (class "Default")
      (node (ref "ISP1") (pin "3") (pinfunction "SCK_3") (pintype "output"))
      (node (ref "U1") (pin "19") (pinfunction "PB5(SCK)_19") (pintype "bidirectional"))
    )
    (net (code "69") (name "SCK2") (class "Default")
      (node (ref "ISP2") (pin "3") (pinfunction "SCK_3") (pintype "output"))
      (node (ref "U2") (pin "19") (pinfunction "PB5(SCK)_19") (pintype "bidirectional"))
    )
    (net (code "70") (name "SCL") (class "Default")
      (node (ref "U1") (pin "28") (pinfunction "PC5(ADC5/SCL)_28") (pintype "bidirectional"))
      (node (ref "U2") (pin "28") (pinfunction "PC5(ADC5/SCL)_28") (pintype "bidirectional"))
    )
    (net (code "71") (name "SDA") (class "Default")
      (node (ref "U1") (pin "27") (pinfunction "PC4(ADC4/SDA)_27") (pintype "bidirectional"))
      (node (ref "U2") (pin "27") (pinfunction "PC4(ADC4/SDA)_27") (pintype "bidirectional"))
    )
    (net (code "72") (name "T1") (class "Default")
      (node (ref "MODESW2") (pin "3") (pinfunction "S_3") (pintype "passive"))
      (node (ref "R11") (pin "P$2") (pinfunction "2_P$2") (pintype "passive"))
      (node (ref "U1") (pin "11") (pinfunction "PD5(T1)_11") (pintype "bidirectional"))
    )
    (net (code "73") (name "T2") (class "Default")
      (node (ref "MODESW2") (pin "1") (pinfunction "O_1") (pintype "passive"))
      (node (ref "R12") (pin "P$2") (pinfunction "2_P$2") (pintype "passive"))
      (node (ref "U1") (pin "6") (pinfunction "PD4(XCK/T0)_6") (pintype "bidirectional"))
    )
    (net (code "74") (name "T3") (class "Default")
      (node (ref "MODESW1") (pin "3") (pinfunction "S_3") (pintype "passive"))
      (node (ref "R2") (pin "P$2") (pinfunction "2_P$2") (pintype "passive"))
      (node (ref "U1") (pin "25") (pinfunction "PC2(ADC2)_25") (pintype "bidirectional"))
    )
    (net (code "75") (name "T4") (class "Default")
      (node (ref "MODESW1") (pin "1") (pinfunction "O_1") (pintype "passive"))
      (node (ref "R3") (pin "P$2") (pinfunction "2_P$2") (pintype "passive"))
      (node (ref "U1") (pin "26") (pinfunction "PC3(ADC3)_26") (pintype "bidirectional"))
    )
    (net (code "76") (name "T5") (class "Default")
      (node (ref "MODESW3") (pin "3") (pinfunction "S_3") (pintype "passive"))
      (node (ref "R5") (pin "P$2") (pinfunction "2_P$2") (pintype "passive"))
      (node (ref "U1") (pin "23") (pinfunction "PC0(ADC0)_23") (pintype "bidirectional"))
    )
    (net (code "77") (name "T6") (class "Default")
      (node (ref "MODESW3") (pin "1") (pinfunction "O_1") (pintype "passive"))
      (node (ref "R6") (pin "P$2") (pinfunction "2_P$2") (pintype "passive"))
      (node (ref "U1") (pin "24") (pinfunction "PC1(ADC1)_24") (pintype "bidirectional"))
    )
    (net (code "78") (name "T7") (class "Default")
      (node (ref "PROGSW") (pin "1") (pinfunction "O_1") (pintype "passive"))
      (node (ref "R21") (pin "P$2") (pinfunction "2_P$2") (pintype "passive"))
      (node (ref "U1") (pin "12") (pinfunction "PD6(AIN0)_12") (pintype "bidirectional"))
    )
    (net (code "79") (name "T8") (class "Default")
      (node (ref "PROGSW") (pin "3") (pinfunction "S_3") (pintype "passive"))
      (node (ref "R20") (pin "P$2") (pinfunction "2_P$2") (pintype "passive"))
      (node (ref "U1") (pin "13") (pinfunction "PD7(AIN1)_13") (pintype "bidirectional"))
    )
    (net (code "80") (name "TRIG") (class "Default")
      (node (ref "R27") (pin "P$1") (pinfunction "1_P$1") (pintype "passive"))
      (node (ref "U1") (pin "4") (pinfunction "PD2(INT0)_4") (pintype "bidirectional"))
      (node (ref "V1") (pin "3") (pinfunction "Y_3") (pintype "open_collector"))
    )
    (net (code "81") (name "TRIGO") (class "Default")
      (node (ref "BUT") (pin "A") (pinfunction "A_A") (pintype "passive"))
      (node (ref "IC1") (pin "3") (pinfunction "+IN_3") (pintype "input"))
      (node (ref "R19") (pin "P$2") (pinfunction "2_P$2") (pintype "passive"))
      (node (ref "U1") (pin "14") (pinfunction "PB0(ICP)_14") (pintype "bidirectional"))
    )
    (net (code "82") (name "unconnected-(C14-Pad2)") (class "Default")
      (node (ref "C14") (pin "2") (pinfunction "2_2") (pintype "passive"))
    )
    (net (code "83") (name "unconnected-(DS1-ANODE_DP-Pad7)") (class "Default")
      (node (ref "DS1") (pin "7") (pinfunction "ANODE_DP_7") (pintype "input"))
    )
    (net (code "84") (name "unconnected-(DS1-ANODE_L1_L2-Pad12)") (class "Default")
      (node (ref "DS1") (pin "12") (pinfunction "ANODE_L1_L2_12") (pintype "input"))
    )
    (net (code "85") (name "unconnected-(DS1-ANODE_L3-Pad9)") (class "Default")
      (node (ref "DS1") (pin "9") (pinfunction "ANODE_L3_9") (pintype "input"))
    )
    (net (code "86") (name "unconnected-(DS1-CATHODE_L3-Pad10)") (class "Default")
      (node (ref "DS1") (pin "10") (pinfunction "CATHODE_L3_10") (pintype "input"))
    )
    (net (code "87") (name "unconnected-(DS1-COMMON_CATHODE_L1_L2-Pad4)") (class "Default")
      (node (ref "DS1") (pin "4") (pinfunction "COMMON_CATHODE_L1_L2_4") (pintype "input"))
    )
    (net (code "88") (name "unconnected-(R34-2-PadP$2)") (class "Default")
      (node (ref "R34") (pin "P$2") (pinfunction "2_P$2") (pintype "passive"))
    )
    (net (code "89") (name "unconnected-(TRIGATEIN-PadNORM)") (class "Default")
      (node (ref "TRIGATEIN") (pin "NORM") (pinfunction "NORM_NORM") (pintype "passive"))
    )
    (net (code "90") (name "unconnected-(TRIGOUT-PadNORM)") (class "Default")
      (node (ref "TRIGOUT") (pin "NORM") (pinfunction "NORM_NORM") (pintype "passive"))
    )
    (net (code "91") (name "unconnected-(TRIGOUT2-PadNORM)") (class "Default")
      (node (ref "TRIGOUT2") (pin "NORM") (pinfunction "NORM_NORM") (pintype "passive"))
    )
    (net (code "92") (name "unconnected-(U1-PD0(RXD)-Pad2)") (class "Default")
      (node (ref "U1") (pin "2") (pinfunction "PD0(RXD)_2") (pintype "bidirectional"))
    )
    (net (code "93") (name "unconnected-(U1-PD1(TXD)-Pad3)") (class "Default")
      (node (ref "U1") (pin "3") (pinfunction "PD1(TXD)_3") (pintype "bidirectional"))
    )
    (net (code "94") (name "unconnected-(U2-PD0(RXD)-Pad2)") (class "Default")
      (node (ref "U2") (pin "2") (pinfunction "PD0(RXD)_2") (pintype "bidirectional"))
    )
    (net (code "95") (name "unconnected-(U2-PD1(TXD)-Pad3)") (class "Default")
      (node (ref "U2") (pin "3") (pinfunction "PD1(TXD)_3") (pintype "bidirectional"))
    )
  )
)
